# temp_sens_ring.net
KiCad netlist of a schematic drawn in EAGLE
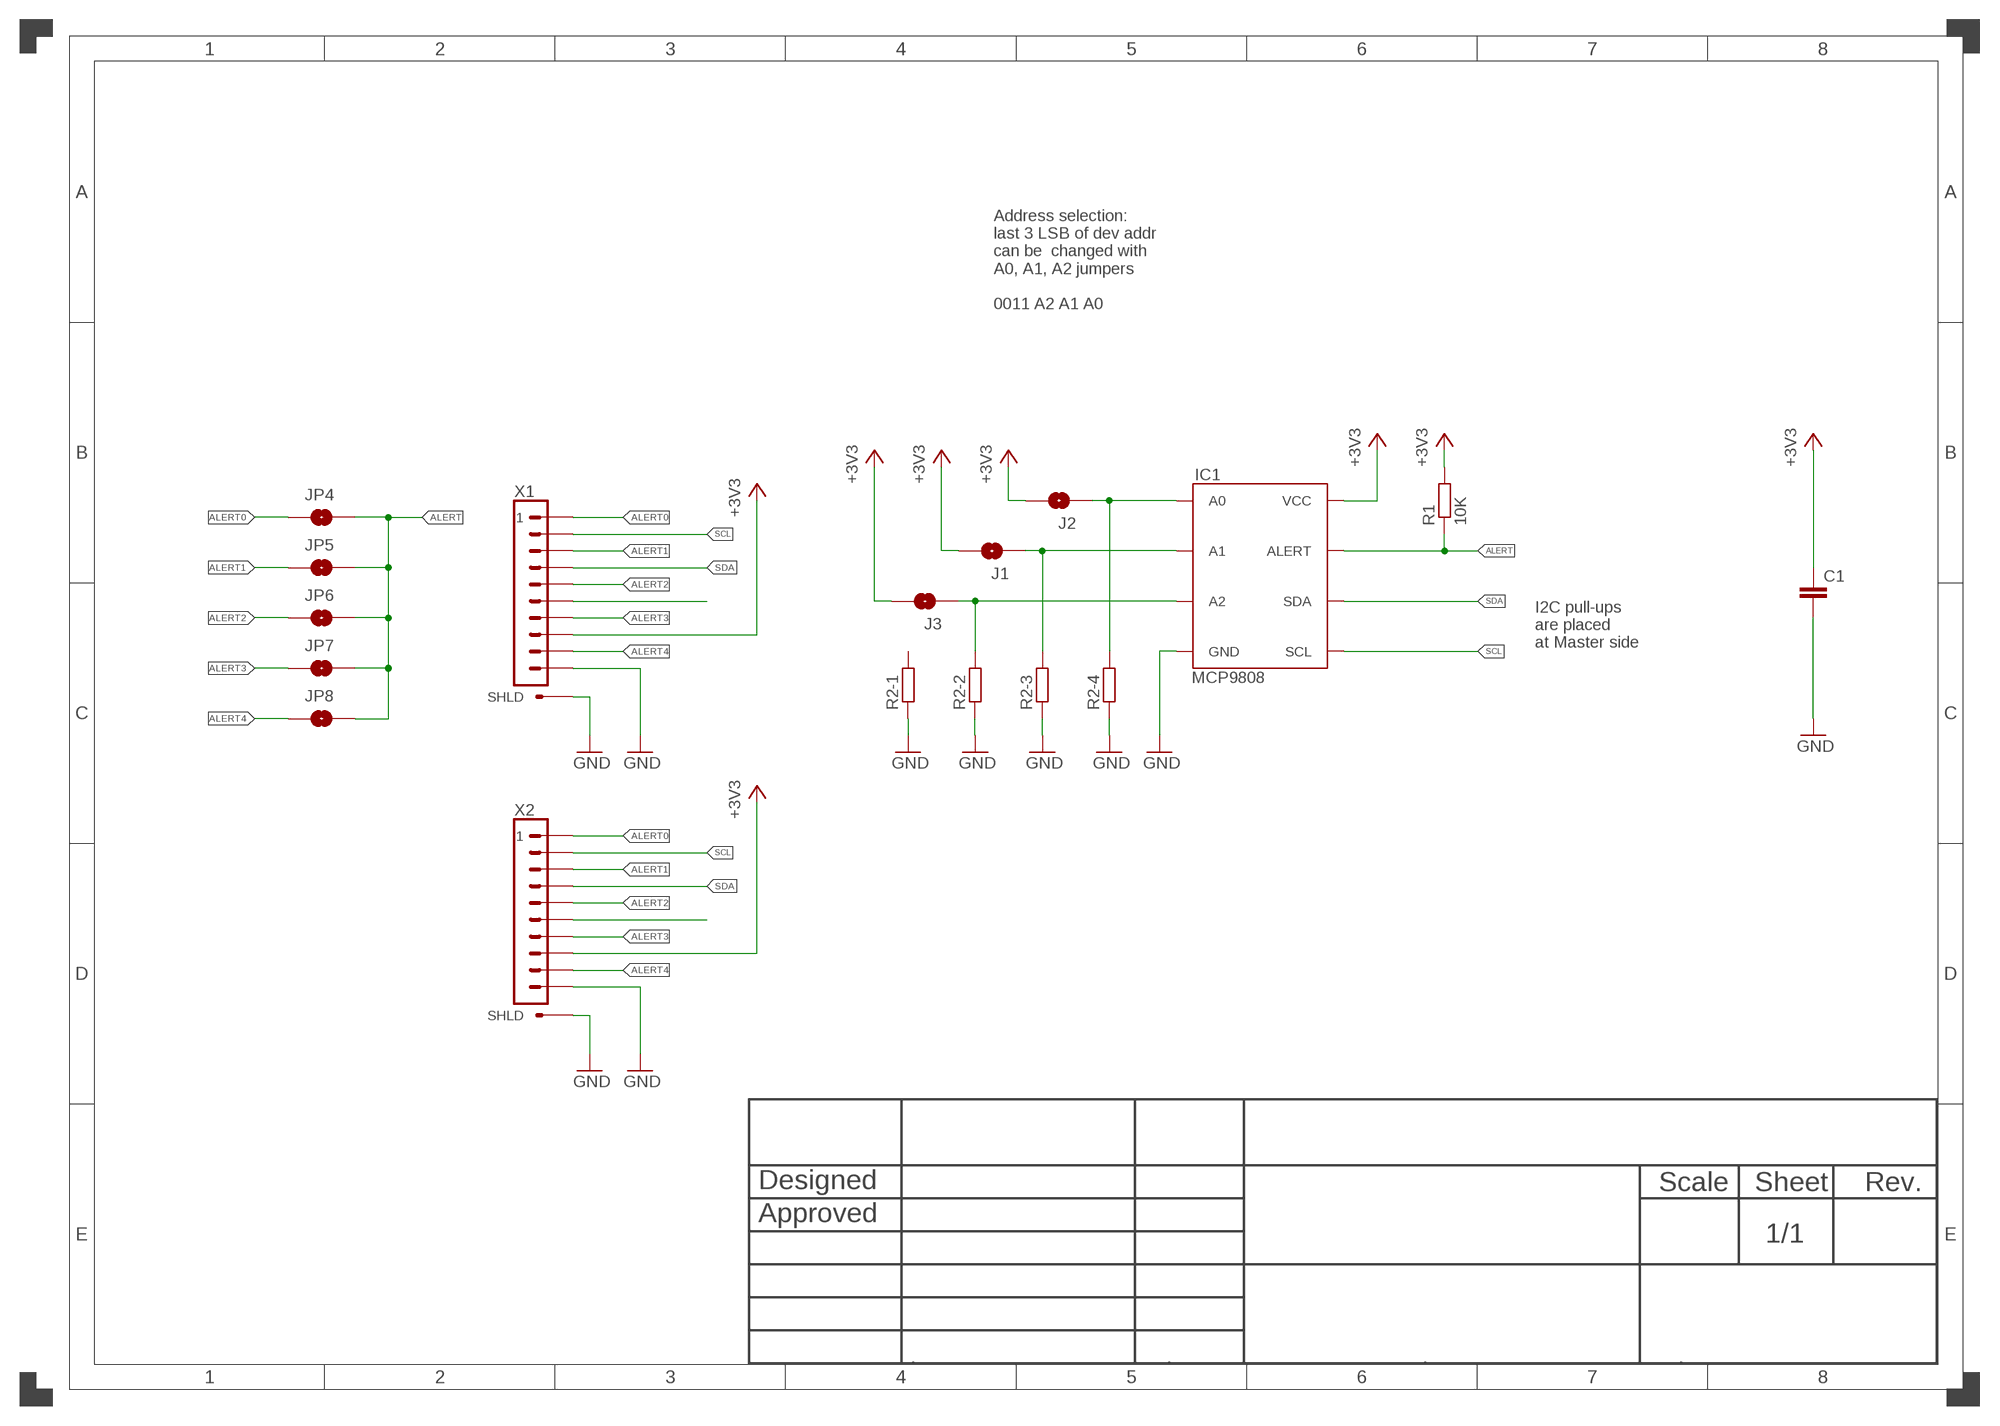
[diagram p0: schematic, sheet 1]

(export (version "E")
  (design (tool "Eeschema 10.0.6"))
  (components
    (comp (ref "C1")
      (value "CAP_CERAMIC_0402")
      (footprint "eagle-import:C0402")
      (libsource (lib "eagle-import") (part "CAP_CERAMIC_0402"))
    )
    (comp (ref "IC1")
      (value "MCP9808")
      (footprint "eagle-import:MSOP-8")
      (libsource (lib "eagle-import") (part "MCP9808"))
    )
    (comp (ref "J1")
      (value "SMD_JUMP_2_NO_S")
      (footprint "eagle-import:SMT_JUMP_2_NO_SMALL")
      (libsource (lib "eagle-import") (part "SMD_JUMP_2_NO_S"))
    )
    (comp (ref "J2")
      (value "SMD_JUMP_2_NO_S")
      (footprint "eagle-import:SMT_JUMP_2_NO_SMALL")
      (libsource (lib "eagle-import") (part "SMD_JUMP_2_NO_S"))
    )
    (comp (ref "J3")
      (value "SMD_JUMP_2_NO_S")
      (footprint "eagle-import:SMT_JUMP_2_NO_SMALL")
      (libsource (lib "eagle-import") (part "SMD_JUMP_2_NO_S"))
    )
    (comp (ref "JP4")
      (value "AL0")
      (footprint "eagle-import:SMT-JUMPER_2_NO_NO-SILK")
      (libsource (lib "eagle-import") (part "JUMPER-SMT_2_NO_NO-SILK"))
    )
    (comp (ref "JP5")
      (value "AL1")
      (footprint "eagle-import:SMT-JUMPER_2_NO_NO-SILK")
      (libsource (lib "eagle-import") (part "JUMPER-SMT_2_NO_NO-SILK"))
    )
    (comp (ref "JP6")
      (value "AL2")
      (footprint "eagle-import:SMT-JUMPER_2_NO_NO-SILK")
      (libsource (lib "eagle-import") (part "JUMPER-SMT_2_NO_NO-SILK"))
    )
    (comp (ref "JP7")
      (value "AL3")
      (footprint "eagle-import:SMT-JUMPER_2_NO_NO-SILK")
      (libsource (lib "eagle-import") (part "JUMPER-SMT_2_NO_NO-SILK"))
    )
    (comp (ref "JP8")
      (value "AL4")
      (footprint "eagle-import:SMT-JUMPER_2_NO_NO-SILK")
      (libsource (lib "eagle-import") (part "JUMPER-SMT_2_NO_NO-SILK"))
    )
    (comp (ref "R1")
      (value "10K")
      (footprint "eagle-import:0402")
      (libsource (lib "eagle-import") (part "RESISTOR_0402"))
    )
    (comp (ref "R2")
      (value "RESISTOR_NET_4-0502")
      (footprint "eagle-import:R0502_4X")
      (libsource (lib "eagle-import") (part "RESISTOR_NET_4-0502"))
    )
    (comp (ref "X1")
      (value "FFC_10PV")
      (footprint "eagle-import:FFC_1X10_VERTICAL")
      (fields
        (field (name "MFR") "XFCN")
        (field (name "MFR_PART") "F1002-B-10-20T-R")
        (field (name "PITCH") "1.00")
      )
      (libsource (lib "eagle-import") (part "FFC_10PV"))
    )
    (comp (ref "X2")
      (value "FFC_10PV")
      (footprint "eagle-import:FFC_1X10_VERTICAL")
      (fields
        (field (name "MFR") "XFCN")
        (field (name "MFR_PART") "F1002-B-10-20T-R")
        (field (name "PITCH") "1.00")
      )
      (libsource (lib "eagle-import") (part "FFC_10PV"))
    )
  )
  (nets
    (net (code "1") (name "+3V3") (class "Default")
      (node (ref "C1") (pin "1") (pinfunction "1_1") (pintype "passive"))
      (node (ref "IC1") (pin "P$8") (pinfunction "VCC_P$8") (pintype "power_in"))
      (node (ref "J1") (pin "2") (pinfunction "2_2") (pintype "passive"))
      (node (ref "J2") (pin "2") (pinfunction "2_2") (pintype "passive"))
      (node (ref "J3") (pin "2") (pinfunction "2_2") (pintype "passive"))
      (node (ref "R1") (pin "2") (pinfunction "2_2") (pintype "passive"))
      (node (ref "X1") (pin "P$8") (pinfunction "8_P$8") (pintype "passive"))
      (node (ref "X2") (pin "P$8") (pinfunction "8_P$8") (pintype "passive"))
    )
    (net (code "2") (name "ALERT") (class "Default")
      (node (ref "IC1") (pin "P$3") (pinfunction "ALERT_P$3") (pintype "output"))
      (node (ref "JP4") (pin "2") (pinfunction "2_2") (pintype "passive"))
      (node (ref "JP5") (pin "2") (pinfunction "2_2") (pintype "passive"))
      (node (ref "JP6") (pin "2") (pinfunction "2_2") (pintype "passive"))
      (node (ref "JP7") (pin "2") (pinfunction "2_2") (pintype "passive"))
      (node (ref "JP8") (pin "2") (pinfunction "2_2") (pintype "passive"))
      (node (ref "R1") (pin "1") (pinfunction "1_1") (pintype "passive"))
    )
    (net (code "3") (name "ALERT0") (class "Default")
      (node (ref "JP4") (pin "1") (pinfunction "1_1") (pintype "passive"))
      (node (ref "X1") (pin "P$1") (pinfunction "1_P$1") (pintype "passive"))
      (node (ref "X2") (pin "P$1") (pinfunction "1_P$1") (pintype "passive"))
    )
    (net (code "4") (name "ALERT1") (class "Default")
      (node (ref "JP5") (pin "1") (pinfunction "1_1") (pintype "passive"))
      (node (ref "X1") (pin "P$3") (pinfunction "3_P$3") (pintype "passive"))
      (node (ref "X2") (pin "P$3") (pinfunction "3_P$3") (pintype "passive"))
    )
    (net (code "5") (name "ALERT2") (class "Default")
      (node (ref "JP6") (pin "1") (pinfunction "1_1") (pintype "passive"))
      (node (ref "X1") (pin "P$5") (pinfunction "5_P$5") (pintype "passive"))
      (node (ref "X2") (pin "P$5") (pinfunction "5_P$5") (pintype "passive"))
    )
    (net (code "6") (name "ALERT3") (class "Default")
      (node (ref "JP7") (pin "1") (pinfunction "1_1") (pintype "passive"))
      (node (ref "X1") (pin "P$7") (pinfunction "7_P$7") (pintype "passive"))
      (node (ref "X2") (pin "P$7") (pinfunction "7_P$7") (pintype "passive"))
    )
    (net (code "7") (name "ALERT4") (class "Default")
      (node (ref "JP8") (pin "1") (pinfunction "1_1") (pintype "passive"))
      (node (ref "X1") (pin "P$9") (pinfunction "9_P$9") (pintype "passive"))
      (node (ref "X2") (pin "P$9") (pinfunction "9_P$9") (pintype "passive"))
    )
    (net (code "8") (name "GND") (class "Default")
      (node (ref "C1") (pin "2") (pinfunction "2_2") (pintype "passive"))
      (node (ref "IC1") (pin "P$4") (pinfunction "GND_P$4") (pintype "power_in"))
      (node (ref "R2") (pin "P$1") (pinfunction "1_P$1") (pintype "passive"))
      (node (ref "R2") (pin "P$2") (pinfunction "1_P$2") (pintype "passive"))
      (node (ref "R2") (pin "P$3") (pinfunction "1_P$3") (pintype "passive"))
      (node (ref "R2") (pin "P$4") (pinfunction "1_P$4") (pintype "passive"))
      (node (ref "X1") (pin "P$10") (pinfunction "10_P$10") (pintype "passive"))
      (node (ref "X1") (pin "P$11") (pinfunction "SHLD_P$11") (pintype "bidirectional"))
      (node (ref "X1") (pin "P$12") (pinfunction "SHLD_P$12") (pintype "bidirectional"))
      (node (ref "X2") (pin "P$10") (pinfunction "10_P$10") (pintype "passive"))
      (node (ref "X2") (pin "P$11") (pinfunction "SHLD_P$11") (pintype "bidirectional"))
      (node (ref "X2") (pin "P$12") (pinfunction "SHLD_P$12") (pintype "bidirectional"))
    )
    (net (code "9") (name "Net-(IC1-A0)") (class "Default")
      (node (ref "IC1") (pin "P$7") (pinfunction "A0_P$7") (pintype "bidirectional"))
      (node (ref "J2") (pin "1") (pinfunction "1_1") (pintype "passive"))
      (node (ref "R2") (pin "P$5") (pinfunction "2_P$5") (pintype "passive"))
    )
    (net (code "10") (name "Net-(IC1-A1)") (class "Default")
      (node (ref "IC1") (pin "P$6") (pinfunction "A1_P$6") (pintype "bidirectional"))
      (node (ref "J1") (pin "1") (pinfunction "1_1") (pintype "passive"))
      (node (ref "R2") (pin "P$6") (pinfunction "2_P$6") (pintype "passive"))
    )
    (net (code "11") (name "Net-(IC1-A2)") (class "Default")
      (node (ref "IC1") (pin "P$5") (pinfunction "A2_P$5") (pintype "bidirectional"))
      (node (ref "J3") (pin "1") (pinfunction "1_1") (pintype "passive"))
      (node (ref "R2") (pin "P$7") (pinfunction "2_P$7") (pintype "passive"))
    )
    (net (code "12") (name "SCL") (class "Default")
      (node (ref "IC1") (pin "P$2") (pinfunction "SCL_P$2") (pintype "bidirectional"))
      (node (ref "X1") (pin "P$2") (pinfunction "2_P$2") (pintype "passive"))
      (node (ref "X2") (pin "P$2") (pinfunction "2_P$2") (pintype "passive"))
    )
    (net (code "13") (name "SDA") (class "Default")
      (node (ref "IC1") (pin "P$1") (pinfunction "SDA_P$1") (pintype "bidirectional"))
      (node (ref "X1") (pin "P$4") (pinfunction "4_P$4") (pintype "passive"))
      (node (ref "X2") (pin "P$4") (pinfunction "4_P$4") (pintype "passive"))
    )
    (net (code "14") (name "unconnected-(R2A-2-PadP$8)") (class "Default")
      (node (ref "R2") (pin "P$8") (pinfunction "2_P$8") (pintype "passive"))
    )
    (net (code "15") (name "unconnected-(X1A-6-PadP$6)") (class "Default")
      (node (ref "X1") (pin "P$6") (pinfunction "6_P$6") (pintype "passive"))
    )
    (net (code "16") (name "unconnected-(X2A-6-PadP$6)") (class "Default")
      (node (ref "X2") (pin "P$6") (pinfunction "6_P$6") (pintype "passive"))
    )
  )
)
